# day_1.net
KiCad netlist of a schematic drawn in EAGLE
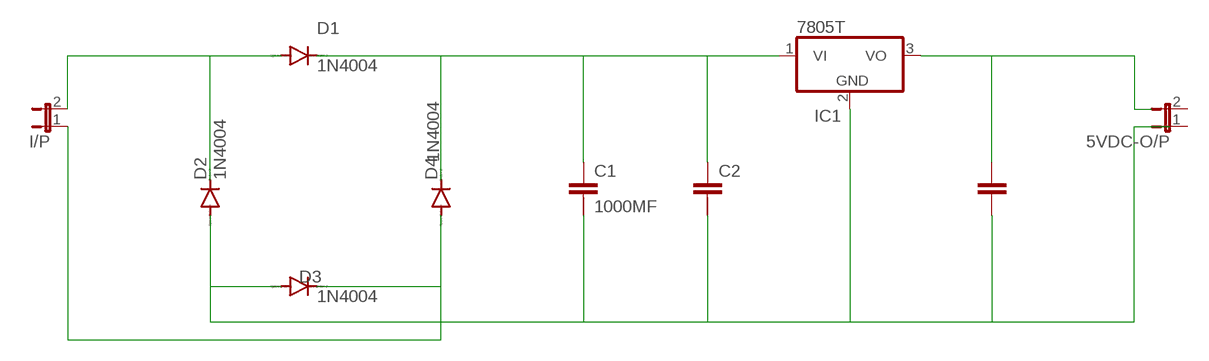
[diagram p0: schematic, sheet 1]

(export (version "E")
  (design (tool "Eeschema 10.0.6"))
  (components
    (comp (ref "5VDC-O/P")
      (value "JP1E")
      (footprint "eagle-import:JP1")
      (libsource (lib "eagle-import") (part "JP1E"))
    )
    (comp (ref "C1")
      (value "1000MF")
      (footprint "eagle-import:C2.5_5-2")
      (libsource (lib "eagle-import") (part "C-2.5-5/2"))
    )
    (comp (ref "C2")
      (value "C-2.5-5/2")
      (footprint "eagle-import:C2.5_5-2")
      (libsource (lib "eagle-import") (part "C-2.5-5/2"))
    )
    (comp (ref "D1")
      (value "1N4004")
      (footprint "eagle-import:DO41-10")
      (libsource (lib "eagle-import") (part "1N4004"))
    )
    (comp (ref "D2")
      (value "1N4004")
      (footprint "eagle-import:DO41-10")
      (libsource (lib "eagle-import") (part "1N4004"))
    )
    (comp (ref "D3")
      (value "1N4004")
      (footprint "eagle-import:DO41-10")
      (libsource (lib "eagle-import") (part "1N4004"))
    )
    (comp (ref "D4")
      (value "1N4004")
      (footprint "eagle-import:DO41-10")
      (libsource (lib "eagle-import") (part "1N4004"))
    )
    (comp (ref "I/P")
      (value "JP1E")
      (footprint "eagle-import:JP1")
      (libsource (lib "eagle-import") (part "JP1E"))
    )
    (comp (ref "IC1")
      (value "7805T")
      (footprint "eagle-import:TO220H")
      (libsource (lib "eagle-import") (part "78T05"))
    )
  )
  (nets
    (net (code "1") (name "Net-(D1-PadA)") (class "Default")
      (node (ref "D1") (pin "A") (pinfunction "A_A") (pintype "passive"))
      (node (ref "D2") (pin "C") (pinfunction "C_C") (pintype "passive"))
      (node (ref "I/P") (pin "2") (pinfunction "2_2") (pintype "passive"))
    )
    (net (code "2") (name "Net-(D3-PadC)") (class "Default")
      (node (ref "D3") (pin "C") (pinfunction "C_C") (pintype "passive"))
      (node (ref "D4") (pin "A") (pinfunction "A_A") (pintype "passive"))
      (node (ref "I/P") (pin "1") (pinfunction "1_1") (pintype "passive"))
    )
    (net (code "3") (name "Net-(IC1-GND)") (class "Default")
      (node (ref "C1") (pin "2") (pinfunction "2_2") (pintype "passive"))
      (node (ref "C2") (pin "2") (pinfunction "2_2") (pintype "passive"))
      (node (ref "D2") (pin "A") (pinfunction "A_A") (pintype "passive"))
      (node (ref "D3") (pin "A") (pinfunction "A_A") (pintype "passive"))
      (node (ref "IC1") (pin "2") (pinfunction "GND_2") (pintype "passive"))
    )
    (net (code "4") (name "Net-(IC1-VI)") (class "Default")
      (node (ref "C1") (pin "1") (pinfunction "1_1") (pintype "passive"))
      (node (ref "C2") (pin "1") (pinfunction "1_1") (pintype "passive"))
      (node (ref "D1") (pin "C") (pinfunction "C_C") (pintype "passive"))
      (node (ref "D4") (pin "C") (pinfunction "C_C") (pintype "passive"))
      (node (ref "IC1") (pin "1") (pinfunction "VI_1") (pintype "input"))
    )
    (net (code "5") (name "unconnected-(5VDC-O/P-Pad1)") (class "Default")
      (node (ref "5VDC-O/P") (pin "1") (pinfunction "1_1") (pintype "passive"))
    )
    (net (code "6") (name "unconnected-(5VDC-O/P-Pad2)") (class "Default")
      (node (ref "5VDC-O/P") (pin "2") (pinfunction "2_2") (pintype "passive"))
    )
    (net (code "7") (name "unconnected-(C1-Pad3)") (class "Default")
      (node (ref "C1") (pin "3") (pinfunction "3_3") (pintype "passive"))
    )
    (net (code "8") (name "unconnected-(C2-Pad3)") (class "Default")
      (node (ref "C2") (pin "3") (pinfunction "3_3") (pintype "passive"))
    )
    (net (code "9") (name "unconnected-(IC1-VO-Pad3)") (class "Default")
      (node (ref "IC1") (pin "3") (pinfunction "VO_3") (pintype "passive"))
    )
  )
)
